# Power.net
KiCad netlist of a schematic drawn in Altium Designer
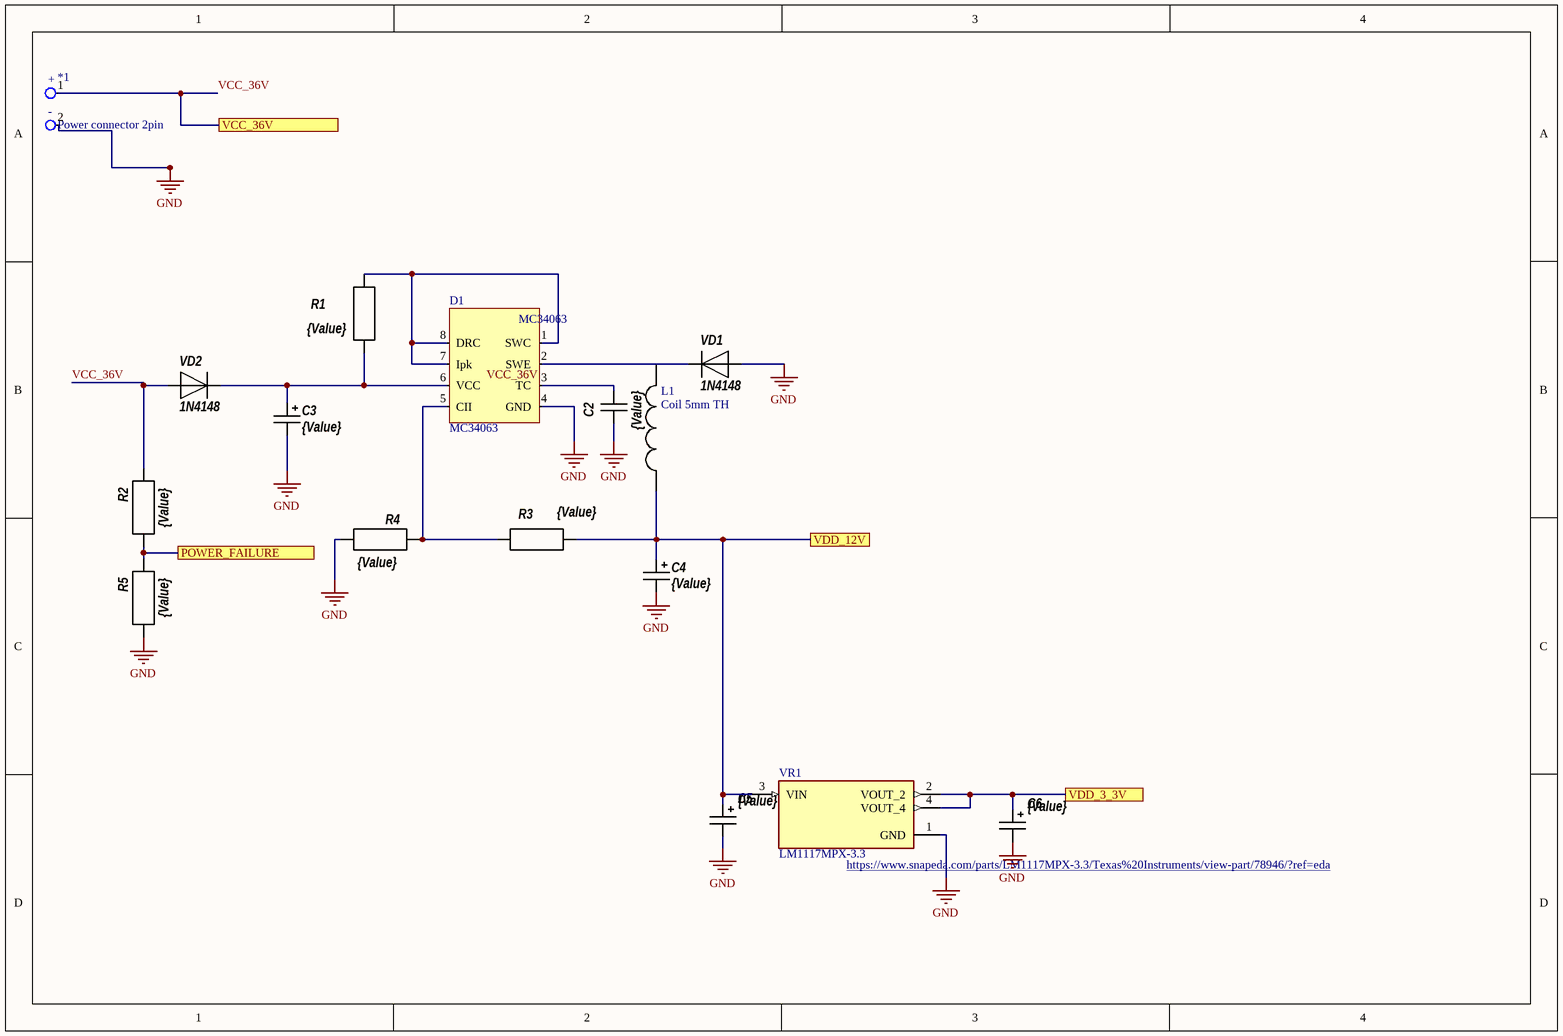
[diagram p0: Power.SchDoc]

(export (version "E")
  (design (tool "Eeschema 10.0.6"))
  (components
    (comp (ref "*1")
      (value "Power connector 2pin")
      (footprint "Power connector 2 pin")
      (libsource (lib "Integrated_Library1") (part "Power connector 2pin"))
    )
    (comp (ref "C2")
      (value "{Value}")
      (footprint "R0805")
      (description "Конденсатор 0805")
      (fields (field (name "MANUFACTURER") "Murata") (field (name "Comment") "Cap 0805"))
      (libsource (lib "УГО") (part "Cap 0805"))
    )
    (comp (ref "C3")
      (value "{Value}")
      (footprint "Cap Alum 8x10.5 mm")
      (description "SMT 8 x 10.5 мм")
      (fields (field (name "MANUFACTURER") "Epcos") (field (name "Comment") "100 uF 50V"))
      (libsource (lib "GIS_SMD components") (part "Cap Alum"))
    )
    (comp (ref "C4")
      (value "{Value}")
      (footprint "Cap Alum 8x10.5 mm")
      (description "SMT 8 x 10.5 мм")
      (fields (field (name "MANUFACTURER") "Epcos") (field (name "Comment") "100 uF 50V"))
      (libsource (lib "GIS_SMD components") (part "Cap Alum"))
    )
    (comp (ref "C5")
      (value "{Value}")
      (footprint "Tantal type B")
      (description "type B")
      (fields (field (name "MANUFACTURER") "AVX") (field (name "Comment") "Cap tan_B"))
      (libsource (lib "GIS_SMD components") (part "Cap tan_B"))
    )
    (comp (ref "C6")
      (value "{Value}")
      (footprint "Tantal type B")
      (description "type B")
      (fields (field (name "MANUFACTURER") "AVX") (field (name "Comment") "Cap tan_B"))
      (libsource (lib "GIS_SMD components") (part "Cap tan_B"))
    )
    (comp (ref "D1")
      (value "MC34063")
      (footprint "MC34063")
      (libsource (lib "Integrated_Library1") (part "MC34063"))
    )
    (comp (ref "L1")
      (value "Coil 5mm TH")
      (footprint "Coil 5mm TH")
      (libsource (lib "Integrated_Library1") (part "Coil 5mm TH"))
    )
    (comp (ref "R1")
      (value "{Value}")
      (footprint "R0805")
      (description "Резистор 0805")
      (fields (field (name "MANUFACTURER") "Yageo") (field (name "Comment") "Res 0805"))
      (libsource (lib "GIS_SMD components") (part "Res 0805"))
    )
    (comp (ref "R2")
      (value "{Value}")
      (footprint "R0805")
      (description "Резистор 0805")
      (fields (field (name "MANUFACTURER") "Yageo") (field (name "Comment") "Res 0805"))
      (libsource (lib "GIS_SMD components") (part "Res 0805"))
    )
    (comp (ref "R3")
      (value "{Value}")
      (footprint "R0805")
      (description "Резистор 0805")
      (fields (field (name "MANUFACTURER") "Yageo") (field (name "Comment") "Res 0805"))
      (libsource (lib "GIS_SMD components") (part "Res 0805"))
    )
    (comp (ref "R4")
      (value "{Value}")
      (footprint "R0805")
      (description "Резистор 0805")
      (fields (field (name "MANUFACTURER") "Yageo") (field (name "Comment") "Res 0805"))
      (libsource (lib "GIS_SMD components") (part "Res 0805"))
    )
    (comp (ref "R5")
      (value "{Value}")
      (footprint "R0805")
      (description "Резистор 0805")
      (fields (field (name "MANUFACTURER") "Yageo") (field (name "Comment") "Res 0805"))
      (libsource (lib "GIS_SMD components") (part "Res 0805"))
    )
    (comp (ref "VD1")
      (value "1N4148")
      (footprint "SOD-80")
      (description "4 ns, 100V, 150 mA")
      (fields (field (name "MANUFACTURER") "NXP"))
      (libsource (lib "GIS_Diods+Bridge") (part "1N4148"))
    )
    (comp (ref "VD2")
      (value "1N4148")
      (footprint "SOD-80")
      (description "4 ns, 100V, 150 mA")
      (fields (field (name "MANUFACTURER") "NXP"))
      (libsource (lib "GIS_Diods+Bridge") (part "1N4148"))
    )
    (comp (ref "VR1")
      (value "LM1117MPX-3.3")
      (footprint "VREG_LM1117MPX-3.3")
      (description "800-mA 15-V linear voltage regulator 4-SOT-223")
      (fields
        (field (name "MF") "Texas Instruments")
        (field (name "CHECK_PRICES") "https://www.snapeda.com/parts/LM1117MPX-3.3/Texas%20Instruments/view-part/78946/?ref=eda")
      )
      (libsource (lib "LM1117MPX-3.3") (part "LM1117MPX-3.3"))
    )
  )
  (nets
    (net (code "1") (name "/POWER_FAILURE") (class "Default")
      (node (ref "R2") (pin "1") (pinfunction "1_1") (pintype "passive"))
      (node (ref "R5") (pin "2") (pinfunction "2_2") (pintype "passive"))
    )
    (net (code "2") (name "/VCC_36V") (class "Default")
      (node (ref "*1") (pin "1") (pintype "passive"))
      (node (ref "R2") (pin "2") (pinfunction "2_2") (pintype "passive"))
      (node (ref "VD2") (pin "1") (pinfunction "1_1") (pintype "passive"))
    )
    (net (code "3") (name "/VDD_3_3V") (class "Default")
      (node (ref "C6") (pin "1") (pinfunction "1_1") (pintype "passive"))
      (node (ref "VR1") (pin "2") (pinfunction "VOUT_2_2") (pintype "output"))
      (node (ref "VR1") (pin "4") (pinfunction "VOUT_4_4") (pintype "output"))
    )
    (net (code "4") (name "/VDD_12V") (class "Default")
      (node (ref "C4") (pin "1") (pinfunction "1_1") (pintype "passive"))
      (node (ref "C5") (pin "1") (pinfunction "1_1") (pintype "passive"))
      (node (ref "L1") (pin "1") (pinfunction "1_1") (pintype "passive"))
      (node (ref "R3") (pin "1") (pinfunction "1_1") (pintype "passive"))
      (node (ref "VR1") (pin "3") (pinfunction "VIN_3") (pintype "input"))
    )
    (net (code "5") (name "GND") (class "Default")
      (node (ref "*1") (pin "2") (pintype "passive"))
      (node (ref "C2") (pin "2") (pinfunction "2_2") (pintype "passive"))
      (node (ref "C3") (pin "2") (pinfunction "2_2") (pintype "passive"))
      (node (ref "C4") (pin "2") (pinfunction "2_2") (pintype "passive"))
      (node (ref "C5") (pin "2") (pinfunction "2_2") (pintype "passive"))
      (node (ref "C6") (pin "2") (pinfunction "2_2") (pintype "passive"))
      (node (ref "D1") (pin "4") (pinfunction "GND_4") (pintype "passive"))
      (node (ref "R4") (pin "1") (pinfunction "1_1") (pintype "passive"))
      (node (ref "R5") (pin "1") (pinfunction "1_1") (pintype "passive"))
      (node (ref "VD1") (pin "1") (pinfunction "1_1") (pintype "passive"))
      (node (ref "VR1") (pin "1") (pinfunction "GND_1") (pintype "power_in"))
    )
    (net (code "6") (name "Net-(D1-CII)") (class "Default")
      (node (ref "D1") (pin "5") (pinfunction "CII_5") (pintype "passive"))
      (node (ref "R3") (pin "2") (pinfunction "2_2") (pintype "passive"))
      (node (ref "R4") (pin "2") (pinfunction "2_2") (pintype "passive"))
    )
    (net (code "7") (name "Net-(D1-DRC)") (class "Default")
      (node (ref "D1") (pin "1") (pinfunction "SWC_1") (pintype "passive"))
      (node (ref "D1") (pin "7") (pinfunction "Ipk_7") (pintype "passive"))
      (node (ref "D1") (pin "8") (pinfunction "DRC_8") (pintype "passive"))
      (node (ref "R1") (pin "1") (pinfunction "1_1") (pintype "passive"))
    )
    (net (code "8") (name "Net-(D1-SWE)") (class "Default")
      (node (ref "D1") (pin "2") (pinfunction "SWE_2") (pintype "passive"))
      (node (ref "L1") (pin "2") (pinfunction "2_2") (pintype "passive"))
      (node (ref "VD1") (pin "2") (pinfunction "2_2") (pintype "passive"))
    )
    (net (code "9") (name "Net-(D1-TC)") (class "Default")
      (node (ref "C2") (pin "1") (pinfunction "1_1") (pintype "passive"))
      (node (ref "D1") (pin "3") (pinfunction "TC_3") (pintype "passive"))
    )
    (net (code "10") (name "Net-(D1-VCC)") (class "Default")
      (node (ref "C3") (pin "1") (pinfunction "1_1") (pintype "passive"))
      (node (ref "D1") (pin "6") (pinfunction "VCC_6") (pintype "passive"))
      (node (ref "R1") (pin "2") (pinfunction "2_2") (pintype "passive"))
      (node (ref "VD2") (pin "2") (pinfunction "2_2") (pintype "passive"))
    )
  )
)
